# AES17Filter.net
KiCad netlist of a schematic drawn in Altium Designer
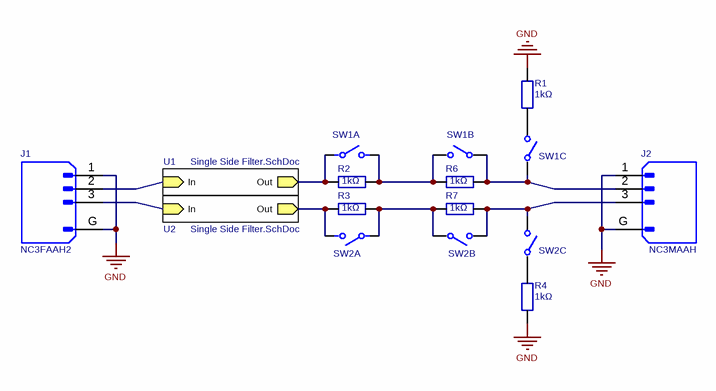
[diagram p0: AES17Filter.SchDoc]

(export (version "E")
  (design (tool "Eeschema 10.0.6"))
  (components
    (comp (ref "J1")
      (value "~")
      (footprint "NEUTRIK_NC3FAAH2")
      (fields (field (name "MPN") "NC3FAAH2"))
      (libsource (lib "Redako") (part "NC3MAAH"))
    )
    (comp (ref "J2")
      (value "~")
      (footprint "NEUTRIK_NC3MAAH")
      (fields (field (name "MPN") "NC3MAAH"))
      (libsource (lib "") (part "NC3MAAH_1"))
    )
    (comp (ref "R1")
      (value "1kΩ")
      (footprint "RESC6432X06N")
      (fields (field (name "TOLERANCE") "1%"))
      (libsource (lib "SchematicLibrary") (part "Res"))
    )
    (comp (ref "R2")
      (value "1kΩ")
      (footprint "RESC6432X06N")
      (fields (field (name "TOLERANCE") "1%"))
      (libsource (lib "SchematicLibrary") (part "Res"))
    )
    (comp (ref "R3")
      (value "1kΩ")
      (footprint "RESC6432X06N")
      (fields (field (name "TOLERANCE") "1%"))
      (libsource (lib "SchematicLibrary") (part "Res"))
    )
    (comp (ref "R4")
      (value "1kΩ")
      (footprint "RESC6432X06N")
      (fields (field (name "TOLERANCE") "1%"))
      (libsource (lib "SchematicLibrary") (part "Res"))
    )
    (comp (ref "R6")
      (value "1kΩ")
      (footprint "RESC6432X06N")
      (fields (field (name "TOLERANCE") "1%"))
      (libsource (lib "SchematicLibrary") (part "Res"))
    )
    (comp (ref "R7")
      (value "1kΩ")
      (footprint "RESC6432X06N")
      (fields (field (name "TOLERANCE") "1%"))
      (libsource (lib "SchematicLibrary") (part "Res"))
    )
    (comp (ref "SW1")
      (value "~")
      (footprint "FP-A6S-3101-H-MFG")
      (description "SWITCH SLIDE DIP SPST 25MA 24V")
      (fields (field (name "MPN") "A6S-3101-H"))
      (libsource (lib "") (part "3494dd441064fb229d3d9931c8c67f4_2"))
    )
    (comp (ref "SW2")
      (value "~")
      (footprint "FP-A6S-3101-H-MFG")
      (description "SWITCH SLIDE DIP SPST 25MA 24V")
      (fields (field (name "MPN") "A6S-3101-H"))
      (libsource (lib "Altium Content Vault") (part "3494dd441064fb229d3d9931c8c67f4"))
    )
  )
  (nets
    (net (code "1") (name "/In") (class "Default")
      (node (ref "J1") (pin "3") (pinfunction "3_3") (pintype "passive"))
    )
    (net (code "2") (name "/In_1") (class "Default")
      (node (ref "J1") (pin "2") (pinfunction "2_2") (pintype "passive"))
    )
    (net (code "3") (name "/Out") (class "Default")
      (node (ref "R2") (pin "1") (pintype "passive"))
      (node (ref "SW1") (pin "1") (pinfunction "1_1") (pintype "passive"))
    )
    (net (code "4") (name "/Out_1") (class "Default")
      (node (ref "R3") (pin "2") (pintype "passive"))
      (node (ref "SW2") (pin "6") (pinfunction "6_6") (pintype "passive"))
    )
    (net (code "5") (name "GND") (class "Default")
      (node (ref "J1") (pin "1") (pinfunction "1_1") (pintype "passive"))
      (node (ref "J1") (pin "G") (pinfunction "G_G") (pintype "power_in"))
      (node (ref "J2") (pin "1") (pinfunction "1_1") (pintype "passive"))
      (node (ref "J2") (pin "G") (pinfunction "G_G") (pintype "power_in"))
      (node (ref "R1") (pin "2") (pintype "passive"))
      (node (ref "R4") (pin "2") (pintype "passive"))
    )
    (net (code "6") (name "Net-(J2-Pad2)") (class "Default")
      (node (ref "J2") (pin "2") (pinfunction "2_2") (pintype "passive"))
      (node (ref "R6") (pin "2") (pintype "passive"))
      (node (ref "SW1") (pin "2") (pinfunction "2_2") (pintype "passive"))
      (node (ref "SW1") (pin "3") (pinfunction "3_3") (pintype "passive"))
    )
    (net (code "7") (name "Net-(J2-Pad3)") (class "Default")
      (node (ref "J2") (pin "3") (pinfunction "3_3") (pintype "passive"))
      (node (ref "R7") (pin "2") (pintype "passive"))
      (node (ref "SW2") (pin "4") (pinfunction "4_4") (pintype "passive"))
      (node (ref "SW2") (pin "5") (pinfunction "5_5") (pintype "passive"))
    )
    (net (code "8") (name "Net-(R1-Pad1)") (class "Default")
      (node (ref "R1") (pin "1") (pintype "passive"))
      (node (ref "SW1") (pin "4") (pinfunction "4_4") (pintype "passive"))
    )
    (net (code "9") (name "Net-(R2-Pad2)") (class "Default")
      (node (ref "R2") (pin "2") (pintype "passive"))
      (node (ref "R6") (pin "1") (pintype "passive"))
      (node (ref "SW1") (pin "5") (pinfunction "5_5") (pintype "passive"))
      (node (ref "SW1") (pin "6") (pinfunction "6_6") (pintype "passive"))
    )
    (net (code "10") (name "Net-(R3-Pad1)") (class "Default")
      (node (ref "R3") (pin "1") (pintype "passive"))
      (node (ref "R7") (pin "1") (pintype "passive"))
      (node (ref "SW2") (pin "1") (pinfunction "1_1") (pintype "passive"))
      (node (ref "SW2") (pin "2") (pinfunction "2_2") (pintype "passive"))
    )
    (net (code "11") (name "Net-(R4-Pad1)") (class "Default")
      (node (ref "R4") (pin "1") (pintype "passive"))
      (node (ref "SW2") (pin "3") (pinfunction "3_3") (pintype "passive"))
    )
  )
)
